# f_bootstrap_cap_boost_L.net
KiCad netlist of a schematic drawn in EAGLE
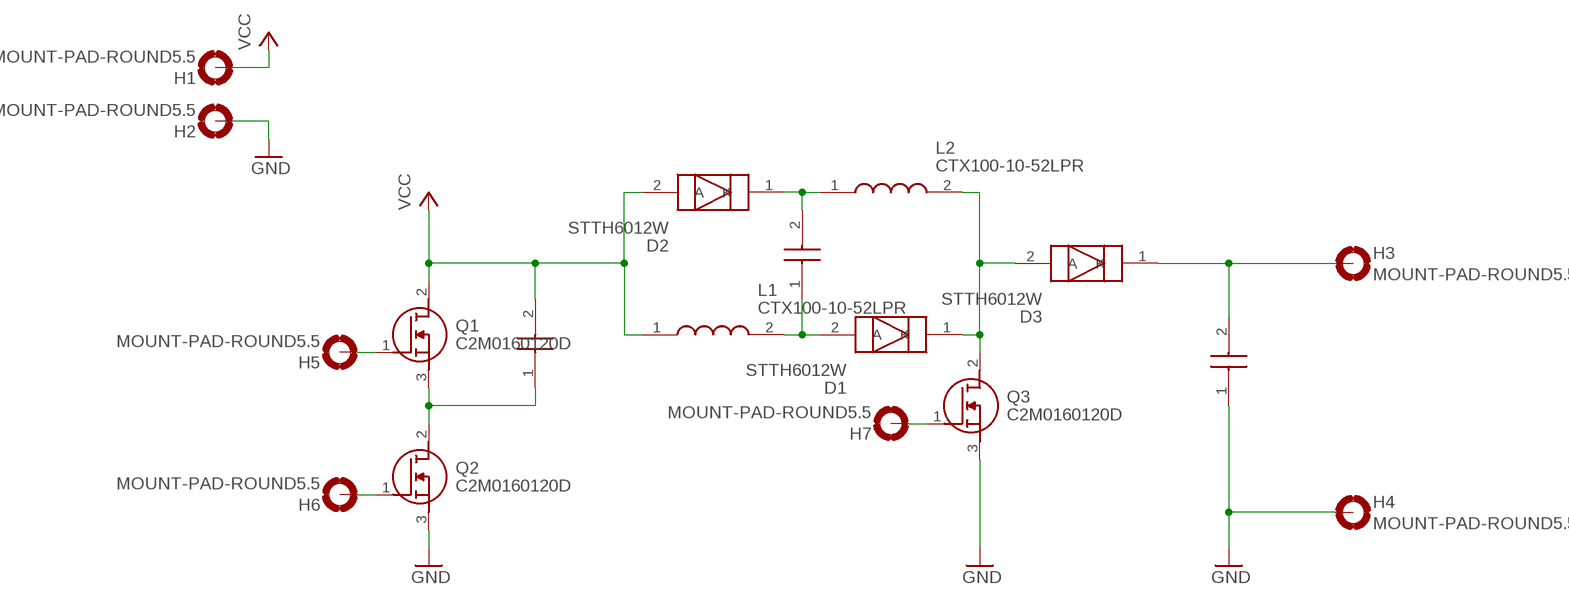
[diagram p0: schematic, sheet 1]

(export (version "E")
  (design (tool "Eeschema 10.0.6"))
  (components
    (comp (ref "C1")
      (value "B32774D4505K000")
      (footprint "eagle-import:B32774D4505K000")
      (fields (field (name "RS_PART_NUMBER") "1726009"))
      (libsource (lib "eagle-import") (part "B32774D4505K000"))
    )
    (comp (ref "C2")
      (value "B32774D4505K000")
      (footprint "eagle-import:B32774D4505K000")
      (fields (field (name "RS_PART_NUMBER") "1726009"))
      (libsource (lib "eagle-import") (part "B32774D4505K000"))
    )
    (comp (ref "D1")
      (value "STTH6012W")
      (footprint "eagle-import:TO1090P515X1560X2445-2P")
      (fields (field (name "RS_PART_NUMBER") "6870818"))
      (libsource (lib "eagle-import") (part "STTH6012W"))
    )
    (comp (ref "D2")
      (value "STTH6012W")
      (footprint "eagle-import:TO1090P515X1560X2445-2P")
      (fields (field (name "RS_PART_NUMBER") "6870818"))
      (libsource (lib "eagle-import") (part "STTH6012W"))
    )
    (comp (ref "D3")
      (value "STTH6012W")
      (footprint "eagle-import:TO1090P515X1560X2445-2P")
      (fields (field (name "RS_PART_NUMBER") "6870818"))
      (libsource (lib "eagle-import") (part "STTH6012W"))
    )
    (comp (ref "H1")
      (value "MOUNT-PAD-ROUND5.5")
      (footprint "eagle-import:5,5-PAD")
      (libsource (lib "eagle-import") (part "MOUNT-PAD-ROUND5.5"))
    )
    (comp (ref "H2")
      (value "MOUNT-PAD-ROUND5.5")
      (footprint "eagle-import:5,5-PAD")
      (libsource (lib "eagle-import") (part "MOUNT-PAD-ROUND5.5"))
    )
    (comp (ref "H3")
      (value "MOUNT-PAD-ROUND5.5")
      (footprint "eagle-import:5,5-PAD")
      (libsource (lib "eagle-import") (part "MOUNT-PAD-ROUND5.5"))
    )
    (comp (ref "H4")
      (value "MOUNT-PAD-ROUND5.5")
      (footprint "eagle-import:5,5-PAD")
      (libsource (lib "eagle-import") (part "MOUNT-PAD-ROUND5.5"))
    )
    (comp (ref "H5")
      (value "MOUNT-PAD-ROUND5.5")
      (footprint "eagle-import:5,5-PAD")
      (libsource (lib "eagle-import") (part "MOUNT-PAD-ROUND5.5"))
    )
    (comp (ref "H6")
      (value "MOUNT-PAD-ROUND5.5")
      (footprint "eagle-import:5,5-PAD")
      (libsource (lib "eagle-import") (part "MOUNT-PAD-ROUND5.5"))
    )
    (comp (ref "H7")
      (value "MOUNT-PAD-ROUND5.5")
      (footprint "eagle-import:5,5-PAD")
      (libsource (lib "eagle-import") (part "MOUNT-PAD-ROUND5.5"))
    )
    (comp (ref "L1")
      (value "CTX100-10-52LPR")
      (footprint "eagle-import:CTX1001052LPR")
      (libsource (lib "eagle-import") (part "CTX100-10-52LPR"))
    )
    (comp (ref "L2")
      (value "CTX100-10-52LPR")
      (footprint "eagle-import:CTX1001052LPR")
      (libsource (lib "eagle-import") (part "CTX100-10-52LPR"))
    )
    (comp (ref "Q1")
      (value "C2M0160120D")
      (footprint "eagle-import:TO544P521X1594X2550-3P")
      (fields (field (name "RS_PART_NUMBER") "1629709"))
      (libsource (lib "eagle-import") (part "C2M0160120D"))
    )
    (comp (ref "Q2")
      (value "C2M0160120D")
      (footprint "eagle-import:TO544P521X1594X2550-3P")
      (fields (field (name "RS_PART_NUMBER") "1629709"))
      (libsource (lib "eagle-import") (part "C2M0160120D"))
    )
    (comp (ref "Q3")
      (value "C2M0160120D")
      (footprint "eagle-import:TO544P521X1594X2550-3P")
      (fields (field (name "RS_PART_NUMBER") "1629709"))
      (libsource (lib "eagle-import") (part "C2M0160120D"))
    )
    (comp (ref "U$1")
      (value "B32774D4505K000")
      (footprint "eagle-import:B32774D4505K000")
      (fields (field (name "RS_PART_NUMBER") "1726009"))
      (libsource (lib "eagle-import") (part "B32774D4505K000"))
    )
  )
  (nets
    (net (code "1") (name "GND") (class "Default")
      (node (ref "C2") (pin "1") (pinfunction "1_1") (pintype "bidirectional"))
      (node (ref "H2") (pin "B5,5") (pinfunction "MOUNT_B5,5") (pintype "passive"))
      (node (ref "H4") (pin "B5,5") (pinfunction "MOUNT_B5,5") (pintype "passive"))
      (node (ref "Q2") (pin "3") (pinfunction "S_3") (pintype "bidirectional"))
      (node (ref "Q3") (pin "3") (pinfunction "S_3") (pintype "bidirectional"))
    )
    (net (code "2") (name "Net-(D1-A)") (class "Default")
      (node (ref "D1") (pin "2") (pinfunction "A_2") (pintype "bidirectional"))
      (node (ref "L1") (pin "2") (pinfunction "2_2") (pintype "bidirectional"))
      (node (ref "U$1") (pin "1") (pinfunction "1_1") (pintype "bidirectional"))
    )
    (net (code "3") (name "Net-(D1-K)") (class "Default")
      (node (ref "D1") (pin "1") (pinfunction "K_1") (pintype "bidirectional"))
      (node (ref "D3") (pin "2") (pinfunction "A_2") (pintype "bidirectional"))
      (node (ref "L2") (pin "2") (pinfunction "2_2") (pintype "bidirectional"))
      (node (ref "Q3") (pin "2") (pinfunction "D_2") (pintype "bidirectional"))
    )
    (net (code "4") (name "Net-(D2-K)") (class "Default")
      (node (ref "D2") (pin "1") (pinfunction "K_1") (pintype "bidirectional"))
      (node (ref "L2") (pin "1") (pinfunction "1_1") (pintype "bidirectional"))
      (node (ref "U$1") (pin "2") (pinfunction "2_2") (pintype "bidirectional"))
    )
    (net (code "5") (name "Net-(D3-K)") (class "Default")
      (node (ref "C2") (pin "2") (pinfunction "2_2") (pintype "bidirectional"))
      (node (ref "D3") (pin "1") (pinfunction "K_1") (pintype "bidirectional"))
      (node (ref "H3") (pin "B5,5") (pinfunction "MOUNT_B5,5") (pintype "passive"))
    )
    (net (code "6") (name "Net-(H5-MOUNT)") (class "Default")
      (node (ref "H5") (pin "B5,5") (pinfunction "MOUNT_B5,5") (pintype "passive"))
      (node (ref "Q1") (pin "1") (pinfunction "G_1") (pintype "bidirectional"))
    )
    (net (code "7") (name "Net-(H6-MOUNT)") (class "Default")
      (node (ref "H6") (pin "B5,5") (pinfunction "MOUNT_B5,5") (pintype "passive"))
      (node (ref "Q2") (pin "1") (pinfunction "G_1") (pintype "bidirectional"))
    )
    (net (code "8") (name "Net-(H7-MOUNT)") (class "Default")
      (node (ref "H7") (pin "B5,5") (pinfunction "MOUNT_B5,5") (pintype "passive"))
      (node (ref "Q3") (pin "1") (pinfunction "G_1") (pintype "bidirectional"))
    )
    (net (code "9") (name "Net-(Q1-S)") (class "Default")
      (node (ref "C1") (pin "1") (pinfunction "1_1") (pintype "bidirectional"))
      (node (ref "Q1") (pin "3") (pinfunction "S_3") (pintype "bidirectional"))
      (node (ref "Q2") (pin "2") (pinfunction "D_2") (pintype "bidirectional"))
    )
    (net (code "10") (name "VCC") (class "Default")
      (node (ref "C1") (pin "2") (pinfunction "2_2") (pintype "bidirectional"))
      (node (ref "D2") (pin "2") (pinfunction "A_2") (pintype "bidirectional"))
      (node (ref "H1") (pin "B5,5") (pinfunction "MOUNT_B5,5") (pintype "passive"))
      (node (ref "L1") (pin "1") (pinfunction "1_1") (pintype "bidirectional"))
      (node (ref "Q1") (pin "2") (pinfunction "D_2") (pintype "bidirectional"))
    )
  )
)
